# controller-board.net
KiCad netlist of a schematic drawn in EAGLE
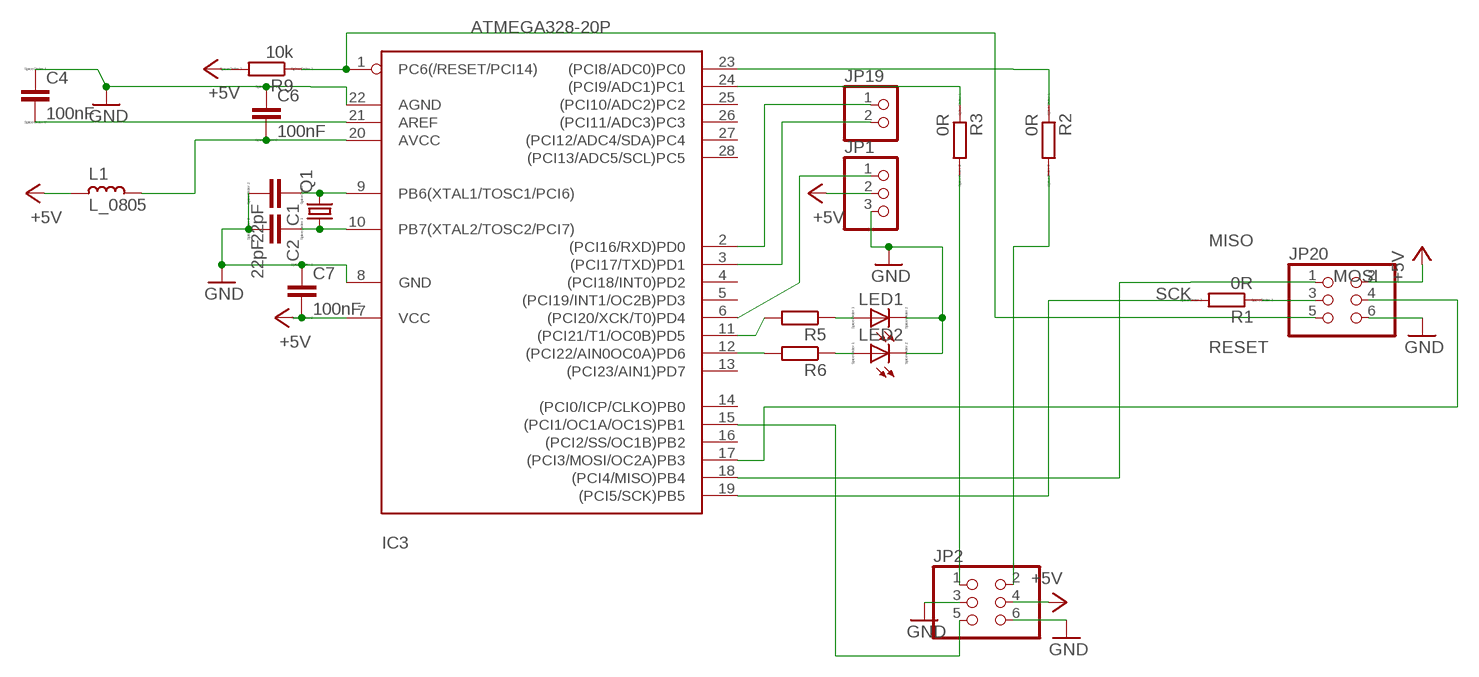
[diagram p0: schematic, sheet 1]

(export (version "E")
  (design (tool "Eeschema 10.0.6"))
  (components
    (comp (ref "C1")
      (value "22pF")
      (footprint "eagle-import:C1206")
      (libsource (lib "eagle-import") (part "CC1206"))
    )
    (comp (ref "C2")
      (value "22pF")
      (footprint "eagle-import:C1206")
      (libsource (lib "eagle-import") (part "CC1206"))
    )
    (comp (ref "C4")
      (value "100nF")
      (footprint "eagle-import:C1206")
      (libsource (lib "eagle-import") (part "CC1206"))
    )
    (comp (ref "C6")
      (value "100nF")
      (footprint "eagle-import:C1206")
      (libsource (lib "eagle-import") (part "CC1206"))
    )
    (comp (ref "C7")
      (value "100nF")
      (footprint "eagle-import:C1206")
      (libsource (lib "eagle-import") (part "CC1206"))
    )
    (comp (ref "IC3")
      (value "ATMEGA328-20P")
      (footprint "eagle-import:DIL28-3")
      (libsource (lib "eagle-import") (part "ATMEGA328P-20"))
    )
    (comp (ref "JP1")
      (value "PINHD-1X3")
      (footprint "eagle-import:1X03")
      (libsource (lib "eagle-import") (part "PINHD-1X3"))
    )
    (comp (ref "JP2")
      (value "PINHD-2X3")
      (footprint "eagle-import:2X03")
      (libsource (lib "eagle-import") (part "PINHD-2X3"))
    )
    (comp (ref "JP19")
      (value "PINHD-1X2")
      (footprint "eagle-import:1X02")
      (libsource (lib "eagle-import") (part "PINHD-1X2"))
    )
    (comp (ref "JP20")
      (value "PINHD-2X3")
      (footprint "eagle-import:2X03")
      (libsource (lib "eagle-import") (part "PINHD-2X3"))
    )
    (comp (ref "L1")
      (value "L_0805")
      (footprint "eagle-import:L0805")
      (libsource (lib "eagle-import") (part "L_0805"))
    )
    (comp (ref "LED1")
      (value "LED_E")
      (footprint "eagle-import:LED_1206")
      (libsource (lib "eagle-import") (part "LED_E"))
    )
    (comp (ref "LED2")
      (value "LED_E")
      (footprint "eagle-import:LED_1206")
      (libsource (lib "eagle-import") (part "LED_E"))
    )
    (comp (ref "Q1")
      (value "CRYSTALHC49U-V")
      (footprint "eagle-import:HC49U-V")
      (libsource (lib "eagle-import") (part "CRYSTALHC49U-V"))
    )
    (comp (ref "R1")
      (value "0R")
      (footprint "eagle-import:R1206")
      (libsource (lib "eagle-import") (part "RR1206"))
    )
    (comp (ref "R2")
      (value "0R")
      (footprint "eagle-import:R1206")
      (libsource (lib "eagle-import") (part "RR1206"))
    )
    (comp (ref "R3")
      (value "0R")
      (footprint "eagle-import:R1206")
      (libsource (lib "eagle-import") (part "RR1206"))
    )
    (comp (ref "R5")
      (value "R-EU_R1206")
      (footprint "eagle-import:R1206")
      (libsource (lib "eagle-import") (part "R-EU_R1206"))
    )
    (comp (ref "R6")
      (value "R-EU_R1206")
      (footprint "eagle-import:R1206")
      (libsource (lib "eagle-import") (part "R-EU_R1206"))
    )
    (comp (ref "R9")
      (value "10k")
      (footprint "eagle-import:R1206")
      (libsource (lib "eagle-import") (part "RR1206"))
    )
  )
  (nets
    (net (code "1") (name "+5V") (class "Default")
      (node (ref "C7") (pin "2") (pinfunction "2_2") (pintype "passive"))
      (node (ref "IC3") (pin "7") (pinfunction "VCC_7") (pintype "bidirectional"))
      (node (ref "JP1") (pin "2") (pinfunction "2_2") (pintype "passive"))
      (node (ref "JP2") (pin "4") (pinfunction "4_4") (pintype "passive"))
      (node (ref "JP20") (pin "2") (pinfunction "2_2") (pintype "passive"))
      (node (ref "L1") (pin "2") (pinfunction "2_2") (pintype "passive"))
      (node (ref "R9") (pin "2") (pinfunction "2_2") (pintype "passive"))
    )
    (net (code "2") (name "/MISO") (class "Default")
      (node (ref "IC3") (pin "18") (pinfunction "(PCI4/MISO)PB4_18") (pintype "bidirectional"))
      (node (ref "JP20") (pin "1") (pinfunction "1_1") (pintype "passive"))
    )
    (net (code "3") (name "/MOSI") (class "Default")
      (node (ref "IC3") (pin "17") (pinfunction "(PCI3/MOSI/OC2A)PB3_17") (pintype "bidirectional"))
      (node (ref "JP20") (pin "4") (pinfunction "4_4") (pintype "passive"))
    )
    (net (code "4") (name "/RESET") (class "Default")
      (node (ref "IC3") (pin "1") (pinfunction "PC6(/RESET/PCI14)_1") (pintype "bidirectional"))
      (node (ref "JP20") (pin "5") (pinfunction "5_5") (pintype "passive"))
      (node (ref "R9") (pin "1") (pinfunction "1_1") (pintype "passive"))
    )
    (net (code "5") (name "/SCK") (class "Default")
      (node (ref "IC3") (pin "19") (pinfunction "(PCI5/SCK)PB5_19") (pintype "bidirectional"))
      (node (ref "R1") (pin "2") (pinfunction "2_2") (pintype "passive"))
    )
    (net (code "6") (name "GND") (class "Default")
      (node (ref "C1") (pin "2") (pinfunction "2_2") (pintype "passive"))
      (node (ref "C2") (pin "2") (pinfunction "2_2") (pintype "passive"))
      (node (ref "C4") (pin "1") (pinfunction "1_1") (pintype "passive"))
      (node (ref "C6") (pin "1") (pinfunction "1_1") (pintype "passive"))
      (node (ref "C7") (pin "1") (pinfunction "1_1") (pintype "passive"))
      (node (ref "IC3") (pin "22") (pinfunction "AGND_22") (pintype "bidirectional"))
      (node (ref "IC3") (pin "8") (pinfunction "GND_8") (pintype "bidirectional"))
      (node (ref "JP1") (pin "3") (pinfunction "3_3") (pintype "passive"))
      (node (ref "JP2") (pin "3") (pinfunction "3_3") (pintype "passive"))
      (node (ref "JP2") (pin "6") (pinfunction "6_6") (pintype "passive"))
      (node (ref "JP20") (pin "6") (pinfunction "6_6") (pintype "passive"))
      (node (ref "LED1") (pin "C") (pinfunction "C_C") (pintype "passive"))
      (node (ref "LED2") (pin "C") (pinfunction "C_C") (pintype "passive"))
    )
    (net (code "7") (name "Net-(IC3-(PCI1{slash}OC1A{slash}OC1S)PB1)") (class "Default")
      (node (ref "IC3") (pin "15") (pinfunction "(PCI1/OC1A/OC1S)PB1_15") (pintype "bidirectional"))
      (node (ref "JP2") (pin "5") (pinfunction "5_5") (pintype "passive"))
    )
    (net (code "8") (name "Net-(IC3-(PCI8{slash}ADC0)PC0)") (class "Default")
      (node (ref "IC3") (pin "23") (pinfunction "(PCI8/ADC0)PC0_23") (pintype "bidirectional"))
      (node (ref "R2") (pin "1") (pinfunction "1_1") (pintype "passive"))
    )
    (net (code "9") (name "Net-(IC3-(PCI9{slash}ADC1)PC1)") (class "Default")
      (node (ref "IC3") (pin "24") (pinfunction "(PCI9/ADC1)PC1_24") (pintype "bidirectional"))
      (node (ref "R3") (pin "1") (pinfunction "1_1") (pintype "passive"))
    )
    (net (code "10") (name "Net-(IC3-(PCI16{slash}RXD)PD0)") (class "Default")
      (node (ref "IC3") (pin "2") (pinfunction "(PCI16/RXD)PD0_2") (pintype "bidirectional"))
      (node (ref "JP19") (pin "1") (pinfunction "1_1") (pintype "passive"))
    )
    (net (code "11") (name "Net-(IC3-(PCI17{slash}TXD)PD1)") (class "Default")
      (node (ref "IC3") (pin "3") (pinfunction "(PCI17/TXD)PD1_3") (pintype "bidirectional"))
      (node (ref "JP19") (pin "2") (pinfunction "2_2") (pintype "passive"))
    )
    (net (code "12") (name "Net-(IC3-(PCI20{slash}XCK{slash}T0)PD4)") (class "Default")
      (node (ref "IC3") (pin "6") (pinfunction "(PCI20/XCK/T0)PD4_6") (pintype "bidirectional"))
      (node (ref "JP1") (pin "1") (pinfunction "1_1") (pintype "passive"))
    )
    (net (code "13") (name "Net-(IC3-(PCI21{slash}T1{slash}OC0B)PD5)") (class "Default")
      (node (ref "IC3") (pin "11") (pinfunction "(PCI21/T1/OC0B)PD5_11") (pintype "bidirectional"))
      (node (ref "R5") (pin "2") (pinfunction "2_2") (pintype "passive"))
    )
    (net (code "14") (name "Net-(IC3-(PCI22{slash}AIN0OC0A)PD6)") (class "Default")
      (node (ref "IC3") (pin "12") (pinfunction "(PCI22/AIN0OC0A)PD6_12") (pintype "bidirectional"))
      (node (ref "R6") (pin "2") (pinfunction "2_2") (pintype "passive"))
    )
    (net (code "15") (name "Net-(IC3-AREF)") (class "Default")
      (node (ref "C4") (pin "2") (pinfunction "2_2") (pintype "passive"))
      (node (ref "IC3") (pin "21") (pinfunction "AREF_21") (pintype "bidirectional"))
    )
    (net (code "16") (name "Net-(IC3-AVCC)") (class "Default")
      (node (ref "C6") (pin "2") (pinfunction "2_2") (pintype "passive"))
      (node (ref "IC3") (pin "20") (pinfunction "AVCC_20") (pintype "bidirectional"))
      (node (ref "L1") (pin "1") (pinfunction "1_1") (pintype "passive"))
    )
    (net (code "17") (name "Net-(IC3-PB6(XTAL1{slash}TOSC1{slash}PCI6))") (class "Default")
      (node (ref "C1") (pin "1") (pinfunction "1_1") (pintype "passive"))
      (node (ref "IC3") (pin "9") (pinfunction "PB6(XTAL1/TOSC1/PCI6)_9") (pintype "bidirectional"))
      (node (ref "Q1") (pin "2") (pinfunction "2_2") (pintype "passive"))
    )
    (net (code "18") (name "Net-(IC3-PB7(XTAL2{slash}TOSC2{slash}PCI7))") (class "Default")
      (node (ref "C2") (pin "1") (pinfunction "1_1") (pintype "passive"))
      (node (ref "IC3") (pin "10") (pinfunction "PB7(XTAL2/TOSC2/PCI7)_10") (pintype "bidirectional"))
      (node (ref "Q1") (pin "1") (pinfunction "1_1") (pintype "passive"))
    )
    (net (code "19") (name "Net-(JP2-Pad1)") (class "Default")
      (node (ref "JP2") (pin "1") (pinfunction "1_1") (pintype "passive"))
      (node (ref "R3") (pin "2") (pinfunction "2_2") (pintype "passive"))
    )
    (net (code "20") (name "Net-(JP2-Pad2)") (class "Default")
      (node (ref "JP2") (pin "2") (pinfunction "2_2") (pintype "passive"))
      (node (ref "R2") (pin "2") (pinfunction "2_2") (pintype "passive"))
    )
    (net (code "21") (name "Net-(JP20-Pad3)") (class "Default")
      (node (ref "JP20") (pin "3") (pinfunction "3_3") (pintype "passive"))
      (node (ref "R1") (pin "1") (pinfunction "1_1") (pintype "passive"))
    )
    (net (code "22") (name "Net-(LED1-PadA)") (class "Default")
      (node (ref "LED1") (pin "A") (pinfunction "A_A") (pintype "passive"))
      (node (ref "R5") (pin "1") (pinfunction "1_1") (pintype "passive"))
    )
    (net (code "23") (name "Net-(LED2-PadA)") (class "Default")
      (node (ref "LED2") (pin "A") (pinfunction "A_A") (pintype "passive"))
      (node (ref "R6") (pin "1") (pinfunction "1_1") (pintype "passive"))
    )
    (net (code "24") (name "unconnected-(IC3-(PCI0{slash}ICP{slash}CLKO)PB0-Pad14)") (class "Default")
      (node (ref "IC3") (pin "14") (pinfunction "(PCI0/ICP/CLKO)PB0_14") (pintype "bidirectional"))
    )
    (net (code "25") (name "unconnected-(IC3-(PCI2{slash}SS{slash}OC1B)PB2-Pad16)") (class "Default")
      (node (ref "IC3") (pin "16") (pinfunction "(PCI2/SS/OC1B)PB2_16") (pintype "bidirectional"))
    )
    (net (code "26") (name "unconnected-(IC3-(PCI10{slash}ADC2)PC2-Pad25)") (class "Default")
      (node (ref "IC3") (pin "25") (pinfunction "(PCI10/ADC2)PC2_25") (pintype "bidirectional"))
    )
    (net (code "27") (name "unconnected-(IC3-(PCI11{slash}ADC3)PC3-Pad26)") (class "Default")
      (node (ref "IC3") (pin "26") (pinfunction "(PCI11/ADC3)PC3_26") (pintype "bidirectional"))
    )
    (net (code "28") (name "unconnected-(IC3-(PCI12{slash}ADC4{slash}SDA)PC4-Pad27)") (class "Default")
      (node (ref "IC3") (pin "27") (pinfunction "(PCI12/ADC4/SDA)PC4_27") (pintype "bidirectional"))
    )
    (net (code "29") (name "unconnected-(IC3-(PCI13{slash}ADC5{slash}SCL)PC5-Pad28)") (class "Default")
      (node (ref "IC3") (pin "28") (pinfunction "(PCI13/ADC5/SCL)PC5_28") (pintype "bidirectional"))
    )
    (net (code "30") (name "unconnected-(IC3-(PCI18{slash}INT0)PD2-Pad4)") (class "Default")
      (node (ref "IC3") (pin "4") (pinfunction "(PCI18/INT0)PD2_4") (pintype "bidirectional"))
    )
    (net (code "31") (name "unconnected-(IC3-(PCI19{slash}INT1{slash}OC2B)PD3-Pad5)") (class "Default")
      (node (ref "IC3") (pin "5") (pinfunction "(PCI19/INT1/OC2B)PD3_5") (pintype "bidirectional"))
    )
    (net (code "32") (name "unconnected-(IC3-(PCI23{slash}AIN1)PD7-Pad13)") (class "Default")
      (node (ref "IC3") (pin "13") (pinfunction "(PCI23/AIN1)PD7_13") (pintype "bidirectional"))
    )
  )
)
